# MUX8.net
KiCad netlist of a schematic drawn in Altium Designer
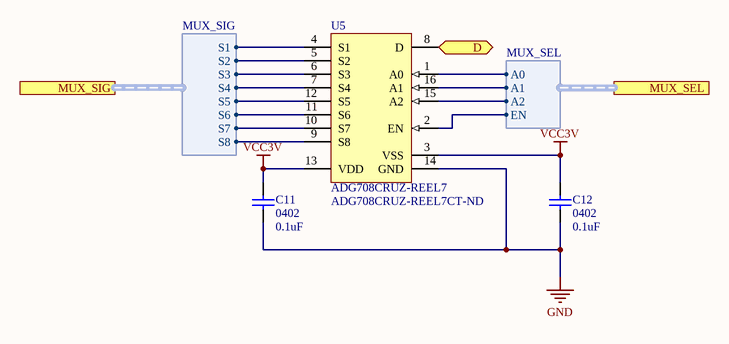
[diagram p0: MUX8.SchDoc]

(export (version "E")
  (design (tool "Eeschema 10.0.6"))
  (components
    (comp (ref "C11")
      (value "0402")
      (footprint "RAD-0.3")
      (description "Capacitor")
      (fields (field (name "ALTIUM_VALUE") "0.1uF") (field (name "PUBLISHER") "Altium Limited"))
      (libsource (lib "Miscellaneous Devices") (part "Cap"))
    )
    (comp (ref "C12")
      (value "0402")
      (footprint "RAD-0.3")
      (description "Capacitor")
      (fields (field (name "ALTIUM_VALUE") "0.1uF") (field (name "PUBLISHER") "Altium Limited"))
      (libsource (lib "Miscellaneous Devices") (part "Cap"))
    )
    (comp (ref "U5")
      (value "ADG708CRUZ-REEL7")
      (footprint "ADI-RU-16_M")
      (fields
        (field (name "MANUFACTURER") "Analog Devices")
        (field (name "SUPPLIER PART NUMBER 1") "ADG708CRUZ-REEL7CT-ND")
      )
      (libsource (lib "heron-general") (part "ADG708CRUZ-REEL7"))
    )
  )
  (nets
    (net (code "3") (name "/A0") (class "Default")
      (node (ref "U5") (pin "1") (pinfunction "A0_1") (pintype "input"))
    )
    (net (code "4") (name "/A1") (class "Default")
      (node (ref "U5") (pin "16") (pinfunction "A1_16") (pintype "input"))
    )
    (net (code "5") (name "/A2") (class "Default")
      (node (ref "U5") (pin "15") (pinfunction "A2_15") (pintype "input"))
    )
    (net (code "6") (name "/D") (class "Default")
      (node (ref "U5") (pin "8") (pinfunction "D_8") (pintype "passive"))
    )
    (net (code "7") (name "/EN") (class "Default")
      (node (ref "U5") (pin "2") (pinfunction "EN_2") (pintype "input"))
    )
    (net (code "8") (name "/S1") (class "Default")
      (node (ref "U5") (pin "4") (pinfunction "S1_4") (pintype "passive"))
    )
    (net (code "9") (name "/S2") (class "Default")
      (node (ref "U5") (pin "5") (pinfunction "S2_5") (pintype "passive"))
    )
    (net (code "10") (name "/S3") (class "Default")
      (node (ref "U5") (pin "6") (pinfunction "S3_6") (pintype "passive"))
    )
    (net (code "11") (name "/S4") (class "Default")
      (node (ref "U5") (pin "7") (pinfunction "S4_7") (pintype "passive"))
    )
    (net (code "12") (name "/S5") (class "Default")
      (node (ref "U5") (pin "12") (pinfunction "S5_12") (pintype "passive"))
    )
    (net (code "13") (name "/S6") (class "Default")
      (node (ref "U5") (pin "11") (pinfunction "S6_11") (pintype "passive"))
    )
    (net (code "14") (name "/S7") (class "Default")
      (node (ref "U5") (pin "10") (pinfunction "S7_10") (pintype "passive"))
    )
    (net (code "15") (name "/S8") (class "Default")
      (node (ref "U5") (pin "9") (pinfunction "S8_9") (pintype "passive"))
    )
    (net (code "18") (name "GND") (class "Default")
      (node (ref "C11") (pin "1") (pinfunction "1_1") (pintype "passive"))
      (node (ref "C12") (pin "1") (pinfunction "1_1") (pintype "passive"))
      (node (ref "U5") (pin "14") (pinfunction "GND_14") (pintype "power_in"))
    )
    (net (code "19") (name "VCC3V") (class "Default")
      (node (ref "C11") (pin "2") (pinfunction "2_2") (pintype "passive"))
      (node (ref "C12") (pin "2") (pinfunction "2_2") (pintype "passive"))
      (node (ref "U5") (pin "13") (pinfunction "VDD_13") (pintype "power_in"))
      (node (ref "U5") (pin "3") (pinfunction "VSS_3") (pintype "power_in"))
    )
  )
)
